# electrode.net
KiCad netlist of a schematic drawn in EAGLE
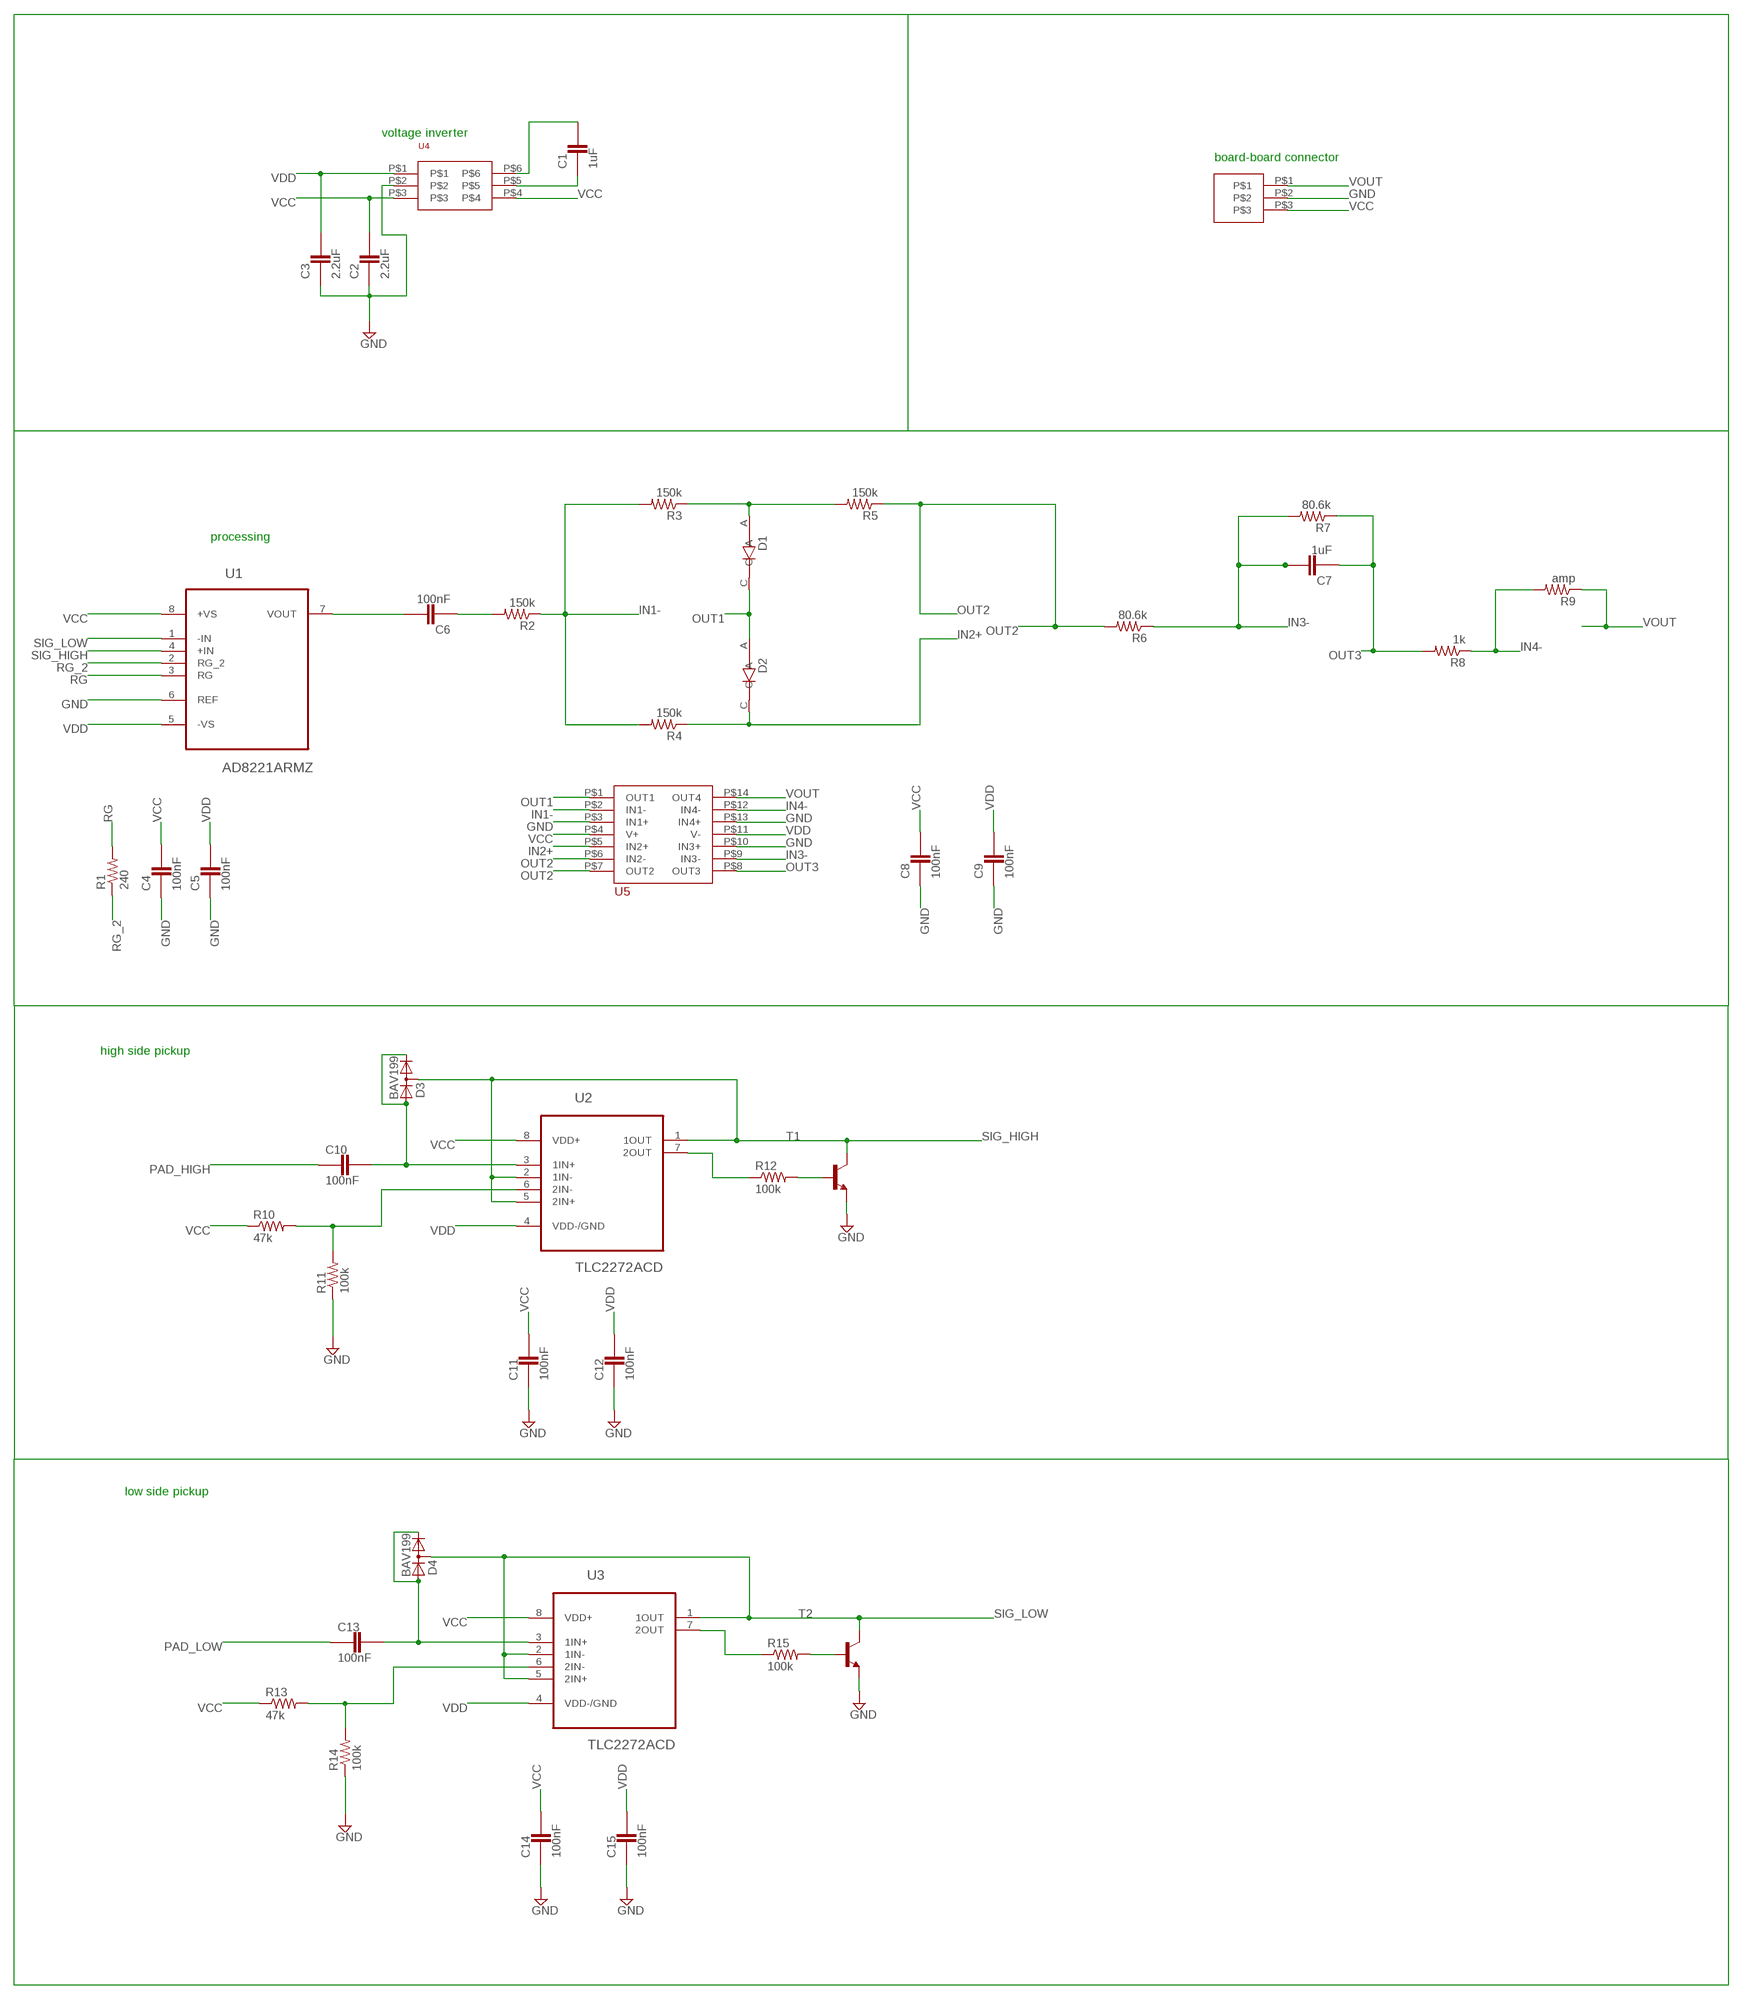
[diagram p0: schematic, sheet 1]

(export (version "E")
  (design (tool "Eeschema 10.0.6"))
  (components
    (comp (ref "C1")
      (value "1uF")
      (footprint "eagle-import:C0603C100C5GACTU_CAPC1608X90")
      (fields (field (name "MANUFACTURER") "KEMET"))
      (libsource (lib "eagle-import") (part "C0603C100C5GACTU"))
    )
    (comp (ref "C2")
      (value "2.2uF")
      (footprint "eagle-import:C0603C100C5GACTU_CAPC1608X90")
      (fields (field (name "MANUFACTURER") "KEMET"))
      (libsource (lib "eagle-import") (part "C0603C100C5GACTU"))
    )
    (comp (ref "C3")
      (value "2.2uF")
      (footprint "eagle-import:C0603C100C5GACTU_CAPC1608X90")
      (fields (field (name "MANUFACTURER") "KEMET"))
      (libsource (lib "eagle-import") (part "C0603C100C5GACTU"))
    )
    (comp (ref "C4")
      (value "100nF")
      (footprint "eagle-import:C0603C100C5GACTU_CAPC1608X90")
      (fields (field (name "MANUFACTURER") "KEMET"))
      (libsource (lib "eagle-import") (part "C0603C100C5GACTU"))
    )
    (comp (ref "C5")
      (value "100nF")
      (footprint "eagle-import:C0603C100C5GACTU_CAPC1608X90")
      (fields (field (name "MANUFACTURER") "KEMET"))
      (libsource (lib "eagle-import") (part "C0603C100C5GACTU"))
    )
    (comp (ref "C6")
      (value "100nF")
      (footprint "eagle-import:C0603C100C5GACTU_CAPC1608X90")
      (fields (field (name "MANUFACTURER") "KEMET"))
      (libsource (lib "eagle-import") (part "C0603C100C5GACTU"))
    )
    (comp (ref "C7")
      (value "1uF")
      (footprint "eagle-import:C0603C100C5GACTU_CAPC1608X90")
      (fields (field (name "MANUFACTURER") "KEMET"))
      (libsource (lib "eagle-import") (part "C0603C100C5GACTU"))
    )
    (comp (ref "C8")
      (value "100nF")
      (footprint "eagle-import:C0603C100C5GACTU_CAPC1608X90")
      (fields (field (name "MANUFACTURER") "KEMET"))
      (libsource (lib "eagle-import") (part "C0603C100C5GACTU"))
    )
    (comp (ref "C9")
      (value "100nF")
      (footprint "eagle-import:C0603C100C5GACTU_CAPC1608X90")
      (fields (field (name "MANUFACTURER") "KEMET"))
      (libsource (lib "eagle-import") (part "C0603C100C5GACTU"))
    )
    (comp (ref "C10")
      (value "100nF")
      (footprint "eagle-import:C0603C100C5GACTU_CAPC1608X90")
      (fields (field (name "MANUFACTURER") "KEMET"))
      (libsource (lib "eagle-import") (part "C0603C100C5GACTU"))
    )
    (comp (ref "C11")
      (value "100nF")
      (footprint "eagle-import:C0603C100C5GACTU_CAPC1608X90")
      (fields (field (name "MANUFACTURER") "KEMET"))
      (libsource (lib "eagle-import") (part "C0603C100C5GACTU"))
    )
    (comp (ref "C12")
      (value "100nF")
      (footprint "eagle-import:C0603C100C5GACTU_CAPC1608X90")
      (fields (field (name "MANUFACTURER") "KEMET"))
      (libsource (lib "eagle-import") (part "C0603C100C5GACTU"))
    )
    (comp (ref "C13")
      (value "100nF")
      (footprint "eagle-import:C0603C100C5GACTU_CAPC1608X90")
      (fields (field (name "MANUFACTURER") "KEMET"))
      (libsource (lib "eagle-import") (part "C0603C100C5GACTU"))
    )
    (comp (ref "C14")
      (value "100nF")
      (footprint "eagle-import:C0603C100C5GACTU_CAPC1608X90")
      (fields (field (name "MANUFACTURER") "KEMET"))
      (libsource (lib "eagle-import") (part "C0603C100C5GACTU"))
    )
    (comp (ref "C15")
      (value "100nF")
      (footprint "eagle-import:C0603C100C5GACTU_CAPC1608X90")
      (fields (field (name "MANUFACTURER") "KEMET"))
      (libsource (lib "eagle-import") (part "C0603C100C5GACTU"))
    )
    (comp (ref "D1")
      (value "1N4148WS-7-F")
      (footprint "eagle-import:SOD2513X120N")
      (fields (field (name "MANUFACTURER") "Diodes Inc."))
      (libsource (lib "eagle-import") (part "1N4148WS-7-F"))
    )
    (comp (ref "D2")
      (value "1N4148WS-7-F")
      (footprint "eagle-import:SOD2513X120N")
      (fields (field (name "MANUFACTURER") "Diodes Inc."))
      (libsource (lib "eagle-import") (part "1N4148WS-7-F"))
    )
    (comp (ref "D3")
      (value "BAV199")
      (footprint "eagle-import:SOT23")
      (libsource (lib "eagle-import") (part "BAV199"))
    )
    (comp (ref "D4")
      (value "BAV199")
      (footprint "eagle-import:SOT23")
      (libsource (lib "eagle-import") (part "BAV199"))
    )
    (comp (ref "R1")
      (value "240")
      (footprint "eagle-import:R0603")
      (libsource (lib "eagle-import") (part "R-US_R0603"))
    )
    (comp (ref "R2")
      (value "150k")
      (footprint "eagle-import:R0603")
      (libsource (lib "eagle-import") (part "R-US_R0603"))
    )
    (comp (ref "R3")
      (value "150k")
      (footprint "eagle-import:R0603")
      (libsource (lib "eagle-import") (part "R-US_R0603"))
    )
    (comp (ref "R4")
      (value "150k")
      (footprint "eagle-import:R0603")
      (libsource (lib "eagle-import") (part "R-US_R0603"))
    )
    (comp (ref "R5")
      (value "150k")
      (footprint "eagle-import:R0603")
      (libsource (lib "eagle-import") (part "R-US_R0603"))
    )
    (comp (ref "R6")
      (value "80.6k")
      (footprint "eagle-import:R0603")
      (libsource (lib "eagle-import") (part "R-US_R0603"))
    )
    (comp (ref "R7")
      (value "80.6k")
      (footprint "eagle-import:R0603")
      (libsource (lib "eagle-import") (part "R-US_R0603"))
    )
    (comp (ref "R8")
      (value "1k")
      (footprint "eagle-import:R0603")
      (libsource (lib "eagle-import") (part "R-US_R0603"))
    )
    (comp (ref "R9")
      (value "amp")
      (footprint "eagle-import:R0603")
      (libsource (lib "eagle-import") (part "R-US_R0603"))
    )
    (comp (ref "R10")
      (value "47k")
      (footprint "eagle-import:R0603")
      (libsource (lib "eagle-import") (part "R-US_R0603"))
    )
    (comp (ref "R11")
      (value "100k")
      (footprint "eagle-import:R0603")
      (libsource (lib "eagle-import") (part "R-US_R0603"))
    )
    (comp (ref "R12")
      (value "100k")
      (footprint "eagle-import:R0603")
      (libsource (lib "eagle-import") (part "R-US_R0603"))
    )
    (comp (ref "R13")
      (value "47k")
      (footprint "eagle-import:R0603")
      (libsource (lib "eagle-import") (part "R-US_R0603"))
    )
    (comp (ref "R14")
      (value "100k")
      (footprint "eagle-import:R0603")
      (libsource (lib "eagle-import") (part "R-US_R0603"))
    )
    (comp (ref "R15")
      (value "100k")
      (footprint "eagle-import:R0603")
      (libsource (lib "eagle-import") (part "R-US_R0603"))
    )
    (comp (ref "T1")
      (value "MMBT2222ALT1-NPN-SOT23-BEC")
      (footprint "eagle-import:SOT23-BEC")
      (libsource (lib "eagle-import") (part "-NPN-SOT23-BECMMBT2222ALT1"))
    )
    (comp (ref "T2")
      (value "MMBT2222ALT1-NPN-SOT23-BEC")
      (footprint "eagle-import:SOT23-BEC")
      (libsource (lib "eagle-import") (part "-NPN-SOT23-BECMMBT2222ALT1"))
    )
    (comp (ref "U$2")
      (value "B3B-PH-SM4")
      (footprint "eagle-import:B3B-PH-SM4")
      (libsource (lib "eagle-import") (part "B3B-PH-SM4"))
    )
    (comp (ref "U1")
      (value "AD8221ARMZ")
      (footprint "eagle-import:SOP65P490X110-8N")
      (fields (field (name "MF") "Analog Devices"))
      (libsource (lib "eagle-import") (part "AD8221ARMZ"))
    )
    (comp (ref "U2")
      (value "TLC2272ACD")
      (footprint "eagle-import:SOIC127P600X175-8N")
      (fields (field (name "MF") "Texas Instruments"))
      (libsource (lib "eagle-import") (part "TLC2272ACD"))
    )
    (comp (ref "U3")
      (value "TLC2272ACD")
      (footprint "eagle-import:SOIC127P600X175-8N")
      (fields (field (name "MF") "Texas Instruments"))
      (libsource (lib "eagle-import") (part "TLC2272ACD"))
    )
    (comp (ref "U4")
      (value "LM2776")
      (footprint "eagle-import:LM2776-SO")
      (libsource (lib "eagle-import") (part "LM2776"))
    )
    (comp (ref "U5")
      (value "TL084")
      (footprint "eagle-import:TL084-TSSOP")
      (libsource (lib "eagle-import") (part "TL084"))
    )
  )
  (nets
    (net (code "1") (name "/IN1-") (class "Default")
      (node (ref "R2") (pin "1") (pinfunction "1_1") (pintype "passive"))
      (node (ref "R3") (pin "2") (pinfunction "2_2") (pintype "passive"))
      (node (ref "R4") (pin "2") (pinfunction "2_2") (pintype "passive"))
      (node (ref "U5") (pin "P$2") (pinfunction "IN1-_P$2") (pintype "bidirectional"))
    )
    (net (code "2") (name "/IN2+") (class "Default")
      (node (ref "D2") (pin "C") (pinfunction "C_C") (pintype "passive"))
      (node (ref "R4") (pin "1") (pinfunction "1_1") (pintype "passive"))
      (node (ref "U5") (pin "P$5") (pinfunction "IN2+_P$5") (pintype "bidirectional"))
    )
    (net (code "3") (name "/IN3-") (class "Default")
      (node (ref "C7") (pin "1") (pinfunction "1_1") (pintype "passive"))
      (node (ref "R6") (pin "1") (pinfunction "1_1") (pintype "passive"))
      (node (ref "R7") (pin "2") (pinfunction "2_2") (pintype "passive"))
      (node (ref "U5") (pin "P$9") (pinfunction "IN3-_P$9") (pintype "bidirectional"))
    )
    (net (code "4") (name "/IN4-") (class "Default")
      (node (ref "R8") (pin "1") (pinfunction "1_1") (pintype "passive"))
      (node (ref "R9") (pin "2") (pinfunction "2_2") (pintype "passive"))
      (node (ref "U5") (pin "P$12") (pinfunction "IN4-_P$12") (pintype "bidirectional"))
    )
    (net (code "5") (name "/OUT1") (class "Default")
      (node (ref "D1") (pin "C") (pinfunction "C_C") (pintype "passive"))
      (node (ref "D2") (pin "A") (pinfunction "A_A") (pintype "passive"))
      (node (ref "U5") (pin "P$1") (pinfunction "OUT1_P$1") (pintype "bidirectional"))
    )
    (net (code "6") (name "/OUT2") (class "Default")
      (node (ref "R5") (pin "1") (pinfunction "1_1") (pintype "passive"))
      (node (ref "R6") (pin "2") (pinfunction "2_2") (pintype "passive"))
      (node (ref "U5") (pin "P$6") (pinfunction "IN2-_P$6") (pintype "bidirectional"))
      (node (ref "U5") (pin "P$7") (pinfunction "OUT2_P$7") (pintype "bidirectional"))
    )
    (net (code "7") (name "/OUT3") (class "Default")
      (node (ref "C7") (pin "2") (pinfunction "2_2") (pintype "passive"))
      (node (ref "R7") (pin "1") (pinfunction "1_1") (pintype "passive"))
      (node (ref "R8") (pin "2") (pinfunction "2_2") (pintype "passive"))
      (node (ref "U5") (pin "P$8") (pinfunction "OUT3_P$8") (pintype "bidirectional"))
    )
    (net (code "8") (name "/PAD_HIGH") (class "Default")
      (node (ref "C10") (pin "2") (pinfunction "2_2") (pintype "passive"))
    )
    (net (code "9") (name "/PAD_LOW") (class "Default")
      (node (ref "C13") (pin "2") (pinfunction "2_2") (pintype "passive"))
    )
    (net (code "10") (name "/RG") (class "Default")
      (node (ref "R1") (pin "2") (pinfunction "2_2") (pintype "passive"))
      (node (ref "U1") (pin "3") (pinfunction "RG_3") (pintype "input"))
    )
    (net (code "11") (name "/RG_2") (class "Default")
      (node (ref "R1") (pin "1") (pinfunction "1_1") (pintype "passive"))
      (node (ref "U1") (pin "2") (pinfunction "RG_2_2") (pintype "input"))
    )
    (net (code "12") (name "/SIG_HIGH") (class "Default")
      (node (ref "D3") (pin "3") (pinfunction "AC_3") (pintype "passive"))
      (node (ref "T1") (pin "C") (pinfunction "C_C") (pintype "passive"))
      (node (ref "U1") (pin "4") (pinfunction "+IN_4") (pintype "input"))
      (node (ref "U2") (pin "1") (pinfunction "1OUT_1") (pintype "output"))
      (node (ref "U2") (pin "2") (pinfunction "1IN-_2") (pintype "input"))
      (node (ref "U2") (pin "5") (pinfunction "2IN+_5") (pintype "input"))
    )
    (net (code "13") (name "/SIG_LOW") (class "Default")
      (node (ref "D4") (pin "3") (pinfunction "AC_3") (pintype "passive"))
      (node (ref "T2") (pin "C") (pinfunction "C_C") (pintype "passive"))
      (node (ref "U1") (pin "1") (pinfunction "-IN_1") (pintype "input"))
      (node (ref "U3") (pin "1") (pinfunction "1OUT_1") (pintype "output"))
      (node (ref "U3") (pin "2") (pinfunction "1IN-_2") (pintype "input"))
      (node (ref "U3") (pin "5") (pinfunction "2IN+_5") (pintype "input"))
    )
    (net (code "14") (name "/VCC") (class "Default")
      (node (ref "C11") (pin "1") (pinfunction "1_1") (pintype "passive"))
      (node (ref "C14") (pin "1") (pinfunction "1_1") (pintype "passive"))
      (node (ref "C2") (pin "1") (pinfunction "1_1") (pintype "passive"))
      (node (ref "C4") (pin "1") (pinfunction "1_1") (pintype "passive"))
      (node (ref "C8") (pin "1") (pinfunction "1_1") (pintype "passive"))
      (node (ref "R10") (pin "1") (pinfunction "1_1") (pintype "passive"))
      (node (ref "R13") (pin "1") (pinfunction "1_1") (pintype "passive"))
      (node (ref "U$2") (pin "P$3") (pinfunction "P$3_P$3") (pintype "bidirectional"))
      (node (ref "U1") (pin "8") (pinfunction "+VS_8") (pintype "power_in"))
      (node (ref "U2") (pin "8") (pinfunction "VDD+_8") (pintype "power_in"))
      (node (ref "U3") (pin "8") (pinfunction "VDD+_8") (pintype "power_in"))
      (node (ref "U4") (pin "P$3") (pinfunction "P$3_P$3") (pintype "bidirectional"))
      (node (ref "U4") (pin "P$4") (pinfunction "P$4_P$4") (pintype "bidirectional"))
      (node (ref "U5") (pin "P$4") (pinfunction "V+_P$4") (pintype "bidirectional"))
    )
    (net (code "15") (name "/VDD") (class "Default")
      (node (ref "C12") (pin "1") (pinfunction "1_1") (pintype "passive"))
      (node (ref "C15") (pin "1") (pinfunction "1_1") (pintype "passive"))
      (node (ref "C3") (pin "1") (pinfunction "1_1") (pintype "passive"))
      (node (ref "C5") (pin "1") (pinfunction "1_1") (pintype "passive"))
      (node (ref "C9") (pin "1") (pinfunction "1_1") (pintype "passive"))
      (node (ref "U1") (pin "5") (pinfunction "-VS_5") (pintype "power_in"))
      (node (ref "U2") (pin "4") (pinfunction "VDD-/GND_4") (pintype "power_in"))
      (node (ref "U3") (pin "4") (pinfunction "VDD-/GND_4") (pintype "power_in"))
      (node (ref "U4") (pin "P$1") (pinfunction "P$1_P$1") (pintype "bidirectional"))
      (node (ref "U5") (pin "P$11") (pinfunction "V-_P$11") (pintype "bidirectional"))
    )
    (net (code "16") (name "/VOUT") (class "Default")
      (node (ref "R9") (pin "1") (pinfunction "1_1") (pintype "passive"))
      (node (ref "U$2") (pin "P$1") (pinfunction "P$1_P$1") (pintype "bidirectional"))
      (node (ref "U5") (pin "P$14") (pinfunction "OUT4_P$14") (pintype "bidirectional"))
    )
    (net (code "17") (name "GND") (class "Default")
      (node (ref "C11") (pin "2") (pinfunction "2_2") (pintype "passive"))
      (node (ref "C12") (pin "2") (pinfunction "2_2") (pintype "passive"))
      (node (ref "C14") (pin "2") (pinfunction "2_2") (pintype "passive"))
      (node (ref "C15") (pin "2") (pinfunction "2_2") (pintype "passive"))
      (node (ref "C2") (pin "2") (pinfunction "2_2") (pintype "passive"))
      (node (ref "C3") (pin "2") (pinfunction "2_2") (pintype "passive"))
      (node (ref "C4") (pin "2") (pinfunction "2_2") (pintype "passive"))
      (node (ref "C5") (pin "2") (pinfunction "2_2") (pintype "passive"))
      (node (ref "C8") (pin "2") (pinfunction "2_2") (pintype "passive"))
      (node (ref "C9") (pin "2") (pinfunction "2_2") (pintype "passive"))
      (node (ref "R11") (pin "1") (pinfunction "1_1") (pintype "passive"))
      (node (ref "R14") (pin "1") (pinfunction "1_1") (pintype "passive"))
      (node (ref "T1") (pin "E") (pinfunction "E_E") (pintype "passive"))
      (node (ref "T2") (pin "E") (pinfunction "E_E") (pintype "passive"))
      (node (ref "U$2") (pin "P$2") (pinfunction "P$2_P$2") (pintype "bidirectional"))
      (node (ref "U1") (pin "6") (pinfunction "REF_6") (pintype "passive"))
      (node (ref "U4") (pin "P$2") (pinfunction "P$2_P$2") (pintype "bidirectional"))
      (node (ref "U5") (pin "P$10") (pinfunction "IN3+_P$10") (pintype "bidirectional"))
      (node (ref "U5") (pin "P$13") (pinfunction "IN4+_P$13") (pintype "bidirectional"))
      (node (ref "U5") (pin "P$3") (pinfunction "IN1+_P$3") (pintype "bidirectional"))
    )
    (net (code "18") (name "Net-(C1-Pad1)") (class "Default")
      (node (ref "C1") (pin "1") (pinfunction "1_1") (pintype "passive"))
      (node (ref "U4") (pin "P$6") (pinfunction "P$6_P$6") (pintype "bidirectional"))
    )
    (net (code "19") (name "Net-(C1-Pad2)") (class "Default")
      (node (ref "C1") (pin "2") (pinfunction "2_2") (pintype "passive"))
      (node (ref "U4") (pin "P$5") (pinfunction "P$5_P$5") (pintype "bidirectional"))
    )
    (net (code "20") (name "Net-(C6-Pad2)") (class "Default")
      (node (ref "C6") (pin "2") (pinfunction "2_2") (pintype "passive"))
      (node (ref "R2") (pin "2") (pinfunction "2_2") (pintype "passive"))
    )
    (net (code "21") (name "Net-(D1-PadA)") (class "Default")
      (node (ref "D1") (pin "A") (pinfunction "A_A") (pintype "passive"))
      (node (ref "R3") (pin "1") (pinfunction "1_1") (pintype "passive"))
      (node (ref "R5") (pin "2") (pinfunction "2_2") (pintype "passive"))
    )
    (net (code "22") (name "Net-(D3-A)") (class "Default")
      (node (ref "C10") (pin "1") (pinfunction "1_1") (pintype "passive"))
      (node (ref "D3") (pin "1") (pinfunction "A_1") (pintype "passive"))
      (node (ref "D3") (pin "2") (pinfunction "C_2") (pintype "passive"))
      (node (ref "U2") (pin "3") (pinfunction "1IN+_3") (pintype "input"))
    )
    (net (code "23") (name "Net-(D4-A)") (class "Default")
      (node (ref "C13") (pin "1") (pinfunction "1_1") (pintype "passive"))
      (node (ref "D4") (pin "1") (pinfunction "A_1") (pintype "passive"))
      (node (ref "D4") (pin "2") (pinfunction "C_2") (pintype "passive"))
      (node (ref "U3") (pin "3") (pinfunction "1IN+_3") (pintype "input"))
    )
    (net (code "24") (name "Net-(R12-Pad2)") (class "Default")
      (node (ref "R12") (pin "2") (pinfunction "2_2") (pintype "passive"))
      (node (ref "T1") (pin "B") (pinfunction "B_B") (pintype "passive"))
    )
    (net (code "25") (name "Net-(R15-Pad2)") (class "Default")
      (node (ref "R15") (pin "2") (pinfunction "2_2") (pintype "passive"))
      (node (ref "T2") (pin "B") (pinfunction "B_B") (pintype "passive"))
    )
    (net (code "26") (name "Net-(U1-VOUT)") (class "Default")
      (node (ref "C6") (pin "1") (pinfunction "1_1") (pintype "passive"))
      (node (ref "U1") (pin "7") (pinfunction "VOUT_7") (pintype "output"))
    )
    (net (code "27") (name "Net-(U2-2IN-)") (class "Default")
      (node (ref "R10") (pin "2") (pinfunction "2_2") (pintype "passive"))
      (node (ref "R11") (pin "2") (pinfunction "2_2") (pintype "passive"))
      (node (ref "U2") (pin "6") (pinfunction "2IN-_6") (pintype "input"))
    )
    (net (code "28") (name "Net-(U2-2OUT)") (class "Default")
      (node (ref "R12") (pin "1") (pinfunction "1_1") (pintype "passive"))
      (node (ref "U2") (pin "7") (pinfunction "2OUT_7") (pintype "output"))
    )
    (net (code "29") (name "Net-(U3-2IN-)") (class "Default")
      (node (ref "R13") (pin "2") (pinfunction "2_2") (pintype "passive"))
      (node (ref "R14") (pin "2") (pinfunction "2_2") (pintype "passive"))
      (node (ref "U3") (pin "6") (pinfunction "2IN-_6") (pintype "input"))
    )
    (net (code "30") (name "Net-(U3-2OUT)") (class "Default")
      (node (ref "R15") (pin "1") (pinfunction "1_1") (pintype "passive"))
      (node (ref "U3") (pin "7") (pinfunction "2OUT_7") (pintype "output"))
    )
  )
)
